# SCH_Hewis_2025-04-20.net
KiCad netlist of a schematic drawn in EasyEDA
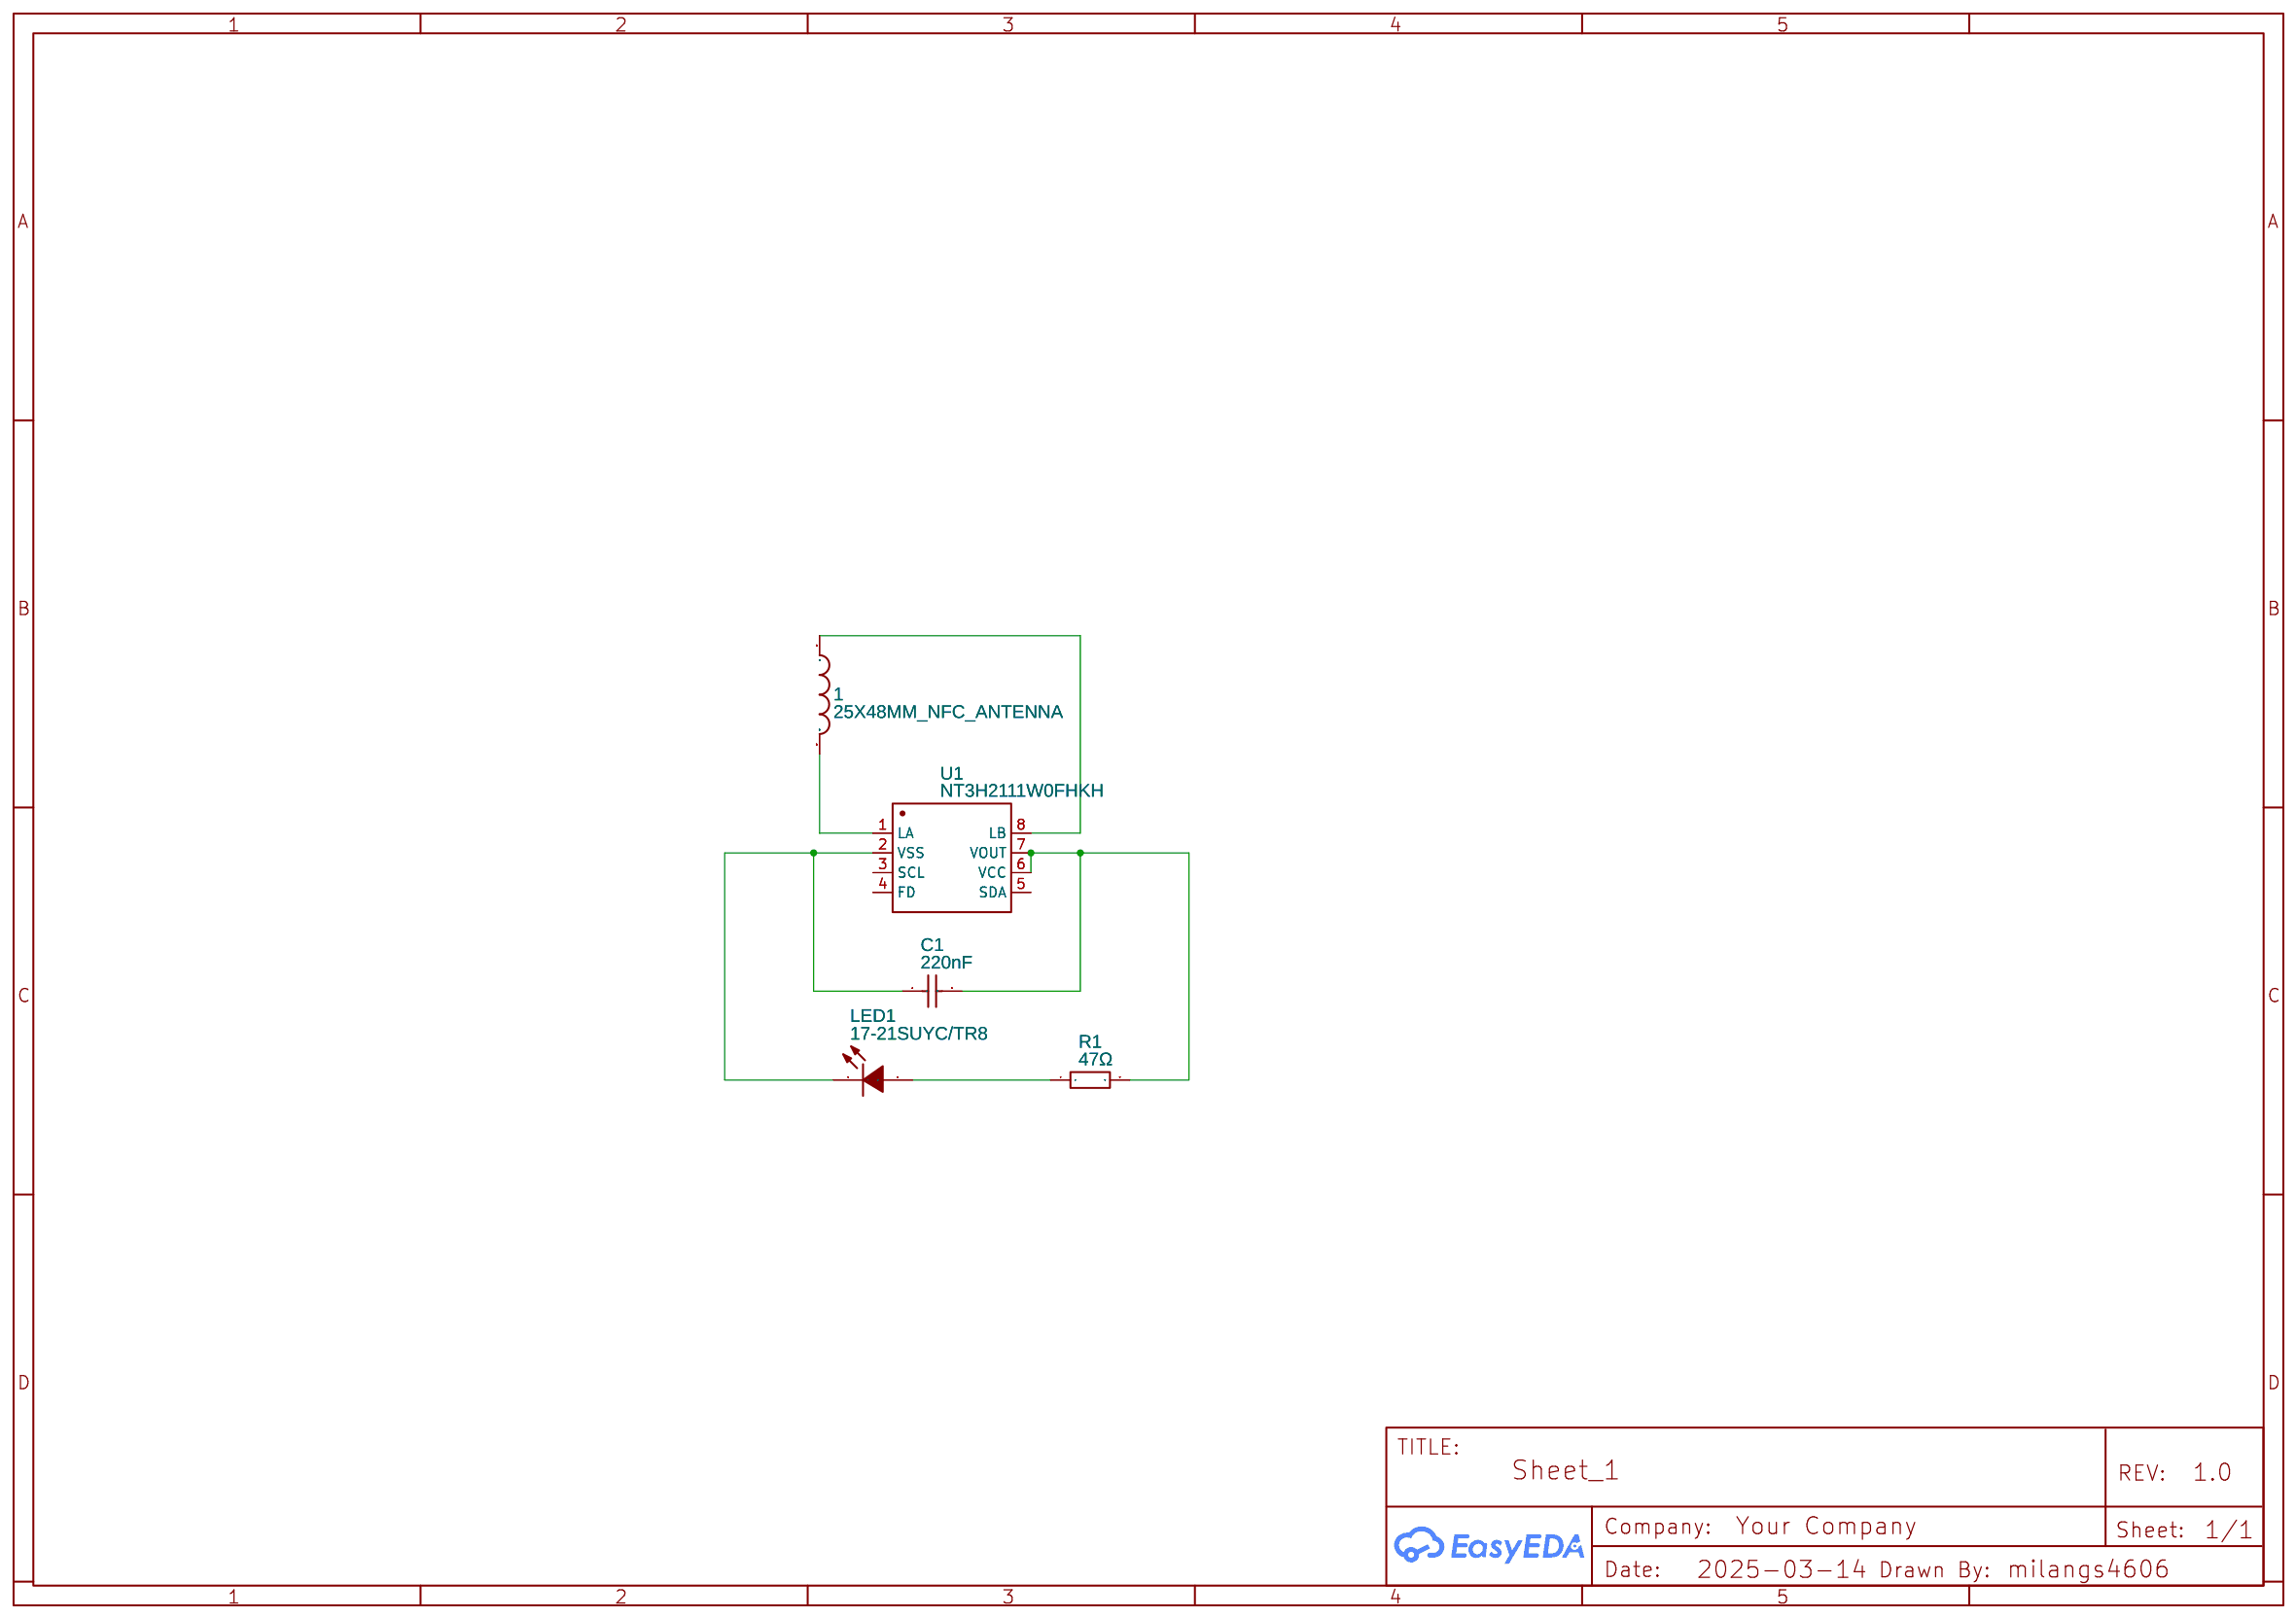
[diagram p0: schematic sheet]

(export (version "E")
  (design (tool "Eeschema 10.0.6"))
  (components
    (comp (ref "1") (value "25X48MM_NFC_ANTENNA") (libsource (lib "") (part "25X48MM_NFC_ANTENNA")))
    (comp (ref "C1")
      (value "220nF")
      (fields
        (field (name "Manufacturer Part") "CL10B224KA8NNNC")
        (field (name "Manufacturer") "SAMSUNG(三星)")
      )
      (libsource (lib "") (part "CL10B224KA8NNNC"))
    )
    (comp (ref "LED1")
      (value "17-21SUYC/TR8")
      (fields (field (name "Manufacturer Part") "KT-0805黄灯") (field (name "Manufacturer") "KENTO"))
      (libsource (lib "") (part "17-21SUYC/TR8"))
    )
    (comp (ref "R1")
      (value "47Ω")
      (fields
        (field (name "Manufacturer Part") "0603WAF470JT5E")
        (field (name "Manufacturer") "UNI-ROYAL(厚声)")
      )
      (libsource (lib "") (part "0603WAF470JT5E"))
    )
    (comp (ref "U1")
      (value "NT3H2111W0FHKH")
      (fields (field (name "Manufacturer") "NXP(恩智浦)"))
      (libsource (lib "") (part "NT3H2111W0FHKH"))
    )
  )
  (nets
    (net (code "1") (name "Net-(LED1-+)") (class "Default")
      (node (ref "LED1") (pin "1") (pinfunction "+_1") (pintype "unspecified"))
      (node (ref "R1") (pin "1") (pinfunction "1_1") (pintype "input"))
    )
    (net (code "2") (name "Net-(LED1--)") (class "Default")
      (node (ref "C1") (pin "1") (pinfunction "1_1") (pintype "input"))
      (node (ref "LED1") (pin "2") (pinfunction "-_2") (pintype "unspecified"))
      (node (ref "U1") (pin "2") (pinfunction "VSS_2") (pintype "unspecified"))
    )
    (net (code "3") (name "Net-(U1-LA)") (class "Default")
      (node (ref "1") (pin "P$2") (pinfunction "P$2_P$2") (pintype "bidirectional"))
      (node (ref "U1") (pin "1") (pinfunction "LA_1") (pintype "unspecified"))
    )
    (net (code "4") (name "Net-(U1-LB)") (class "Default")
      (node (ref "1") (pin "P$1") (pinfunction "P$1_P$1") (pintype "bidirectional"))
      (node (ref "U1") (pin "8") (pinfunction "LB_8") (pintype "unspecified"))
    )
    (net (code "5") (name "Net-(U1-VCC)") (class "Default")
      (node (ref "C1") (pin "2") (pinfunction "2_2") (pintype "input"))
      (node (ref "R1") (pin "2") (pinfunction "2_2") (pintype "input"))
      (node (ref "U1") (pin "6") (pinfunction "VCC_6") (pintype "unspecified"))
      (node (ref "U1") (pin "7") (pinfunction "VOUT_7") (pintype "unspecified"))
    )
    (net (code "6") (name "unconnected-(U1-FD-Pad4)") (class "Default")
      (node (ref "U1") (pin "4") (pinfunction "FD_4") (pintype "unspecified"))
    )
    (net (code "7") (name "unconnected-(U1-SCL-Pad3)") (class "Default")
      (node (ref "U1") (pin "3") (pinfunction "SCL_3") (pintype "unspecified"))
    )
    (net (code "8") (name "unconnected-(U1-SDA-Pad5)") (class "Default")
      (node (ref "U1") (pin "5") (pinfunction "SDA_5") (pintype "unspecified"))
    )
  )
)
